# switch_eval_box_redo_v2.net
KiCad netlist of a schematic drawn in EAGLE
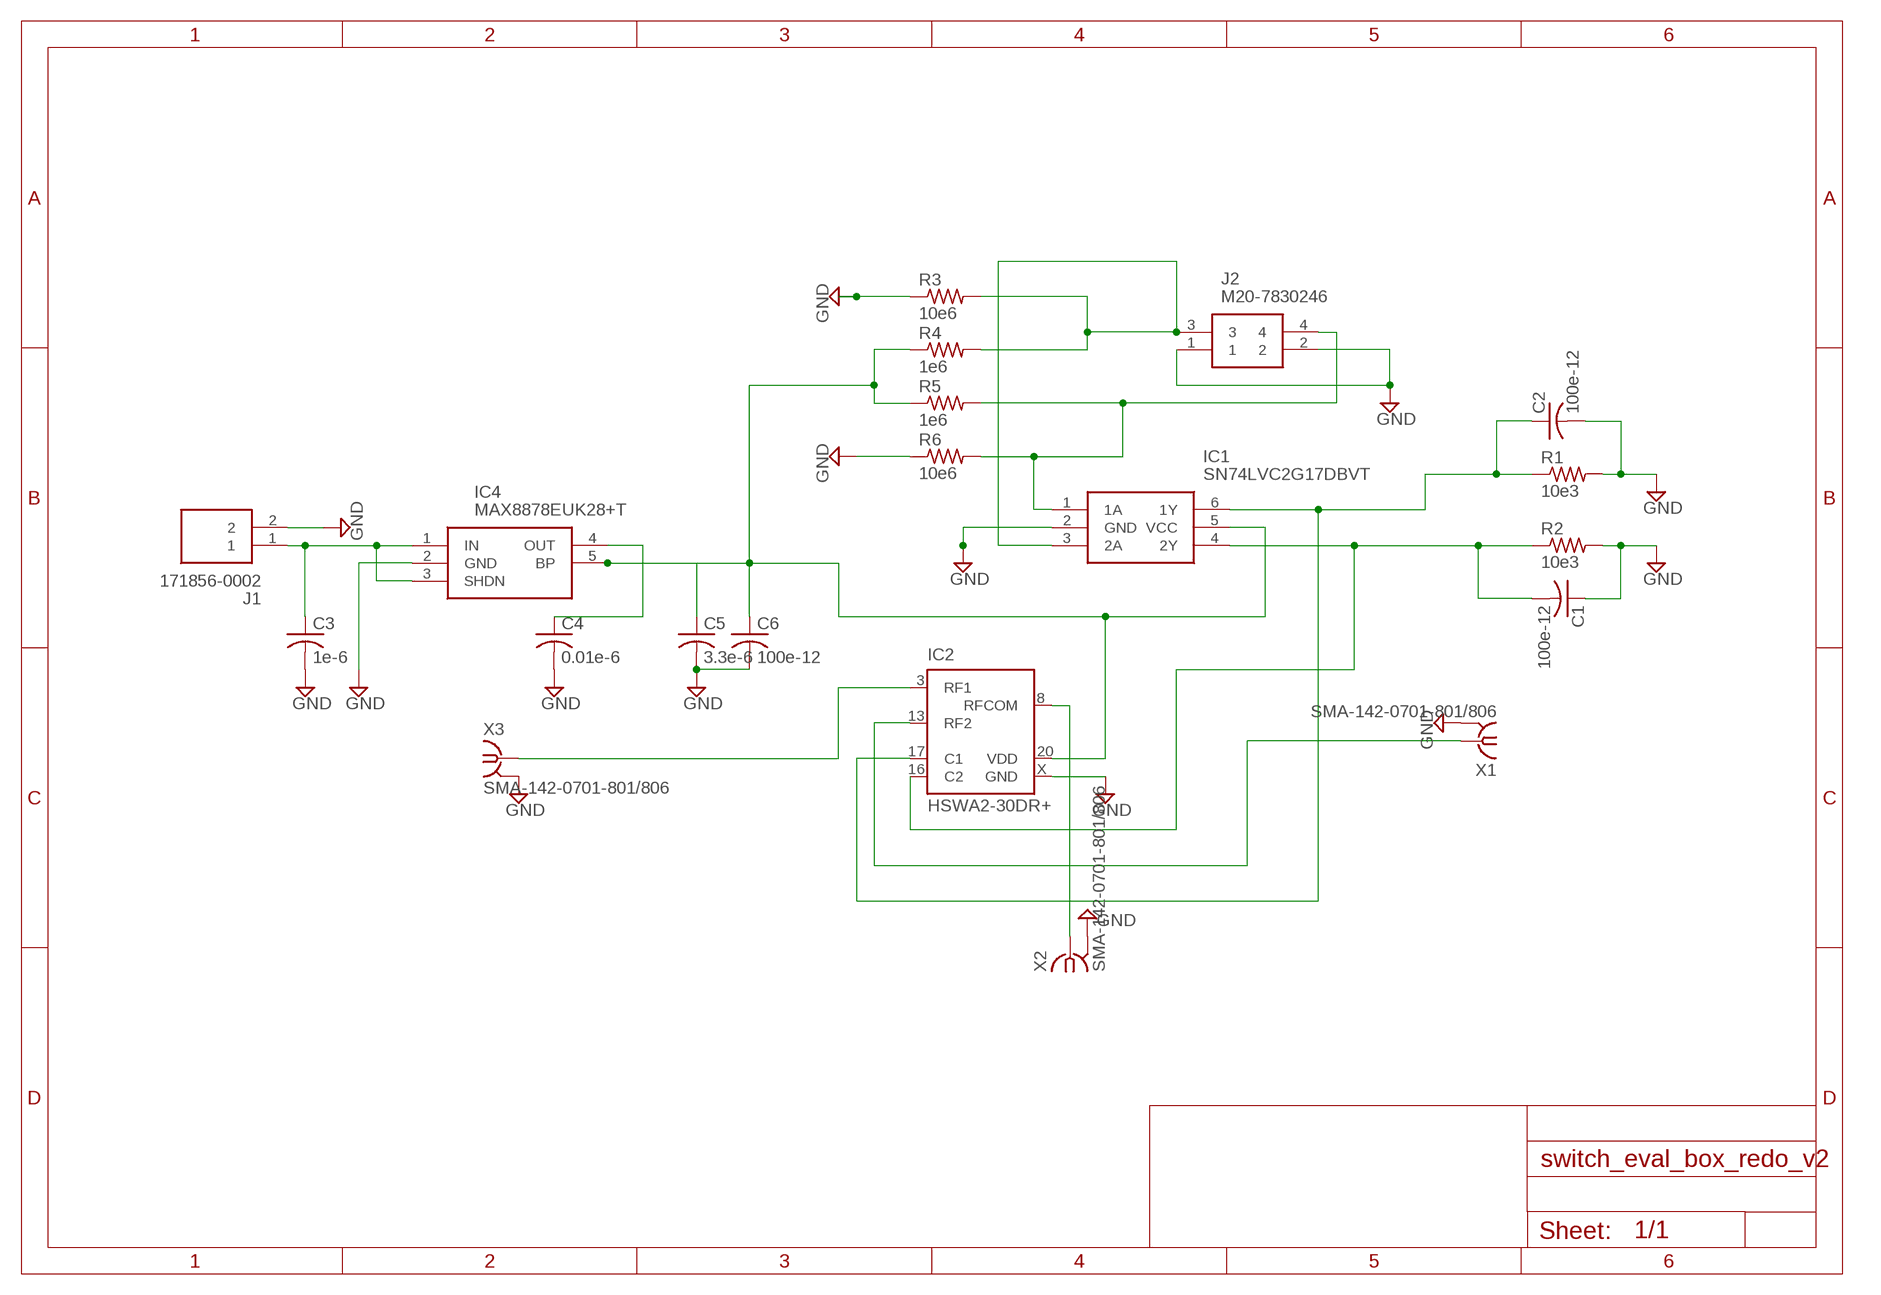
[diagram p0: schematic, sheet 1]

(export (version "E")
  (design (tool "Eeschema 10.0.6"))
  (components
    (comp (ref "C1")
      (value "100e-12")
      (footprint "eagle-import:C0603")
      (libsource (lib "eagle-import") (part "C-USC0603"))
    )
    (comp (ref "C2")
      (value "100e-12")
      (footprint "eagle-import:C0603")
      (libsource (lib "eagle-import") (part "C-USC0603"))
    )
    (comp (ref "C3")
      (value "1e-6")
      (footprint "eagle-import:C0603")
      (libsource (lib "eagle-import") (part "C-USC0603"))
    )
    (comp (ref "C4")
      (value "0.01e-6")
      (footprint "eagle-import:C0603")
      (libsource (lib "eagle-import") (part "C-USC0603"))
    )
    (comp (ref "C5")
      (value "3.3e-6")
      (footprint "eagle-import:C0603")
      (libsource (lib "eagle-import") (part "C-USC0603"))
    )
    (comp (ref "C6")
      (value "100e-12")
      (footprint "eagle-import:C0603")
      (libsource (lib "eagle-import") (part "C-USC0603"))
    )
    (comp (ref "IC1")
      (value "SN74LVC2G17DBVT")
      (footprint "eagle-import:SOT95P280X145-6N")
      (fields
        (field (name "MOUSER_PART_NUMBER") "595-SN74LVC2G17DBVT")
        (field (name "RS_PART_NUMBER") "6628944P")
      )
      (libsource (lib "eagle-import") (part "SN74LVC2G17DBVT"))
    )
    (comp (ref "IC2")
      (value "HSWA2-30DR+")
      (footprint "eagle-import:DG983-1")
      (libsource (lib "eagle-import") (part "HSWA2-30DR+"))
    )
    (comp (ref "IC4")
      (value "MAX8878EUK28+T")
      (footprint "eagle-import:SOT95P280X145-5N")
      (libsource (lib "eagle-import") (part "MAX8878EUK28+T"))
    )
    (comp (ref "J1")
      (value "171856-0002")
      (footprint "eagle-import:SHDR2W90P0X254_1X2_493X635X106")
      (fields
        (field (name "MOUSER_PART_NUMBER") "538-171856-0002")
        (field (name "RS_PART_NUMBER") "7922884P")
      )
      (libsource (lib "eagle-import") (part "171856-0002"))
    )
    (comp (ref "J2")
      (value "M20-7830246")
      (footprint "eagle-import:M207830246")
      (fields
        (field (name "MOUSER_PART_NUMBER") "855-M20-7830246")
        (field (name "RS_PART_NUMBER") "6816839P")
      )
      (libsource (lib "eagle-import") (part "M20-7830246"))
    )
    (comp (ref "R1")
      (value "10e3")
      (footprint "eagle-import:R0603")
      (libsource (lib "eagle-import") (part "R-US_R0603"))
    )
    (comp (ref "R2")
      (value "10e3")
      (footprint "eagle-import:R0603")
      (libsource (lib "eagle-import") (part "R-US_R0603"))
    )
    (comp (ref "R3")
      (value "10e6")
      (footprint "eagle-import:R0603")
      (libsource (lib "eagle-import") (part "R-US_R0603"))
    )
    (comp (ref "R4")
      (value "1e6")
      (footprint "eagle-import:R0603")
      (libsource (lib "eagle-import") (part "R-US_R0603"))
    )
    (comp (ref "R5")
      (value "1e6")
      (footprint "eagle-import:R0603")
      (libsource (lib "eagle-import") (part "R-US_R0603"))
    )
    (comp (ref "R6")
      (value "10e6")
      (footprint "eagle-import:R0603")
      (libsource (lib "eagle-import") (part "R-US_R0603"))
    )
    (comp (ref "X1")
      (value "SMA-142-0701-801/806")
      (footprint "eagle-import:J502-ND-142-0701-801_806")
      (fields (field (name "MF") "JOHNSON COMPONENTS") (field (name "MPN") "142-0701-801"))
      (libsource (lib "eagle-import") (part "SMA-142-0701-801/806"))
    )
    (comp (ref "X2")
      (value "SMA-142-0701-801/806")
      (footprint "eagle-import:J502-ND-142-0701-801_806")
      (fields (field (name "MF") "JOHNSON COMPONENTS") (field (name "MPN") "142-0701-801"))
      (libsource (lib "eagle-import") (part "SMA-142-0701-801/806"))
    )
    (comp (ref "X3")
      (value "SMA-142-0701-801/806")
      (footprint "eagle-import:J502-ND-142-0701-801_806")
      (fields (field (name "MF") "JOHNSON COMPONENTS") (field (name "MPN") "142-0701-801"))
      (libsource (lib "eagle-import") (part "SMA-142-0701-801/806"))
    )
  )
  (nets
    (net (code "1") (name "GND") (class "Default")
      (node (ref "C1") (pin "1") (pinfunction "1_1") (pintype "passive"))
      (node (ref "C2") (pin "2") (pinfunction "2_2") (pintype "passive"))
      (node (ref "C3") (pin "2") (pinfunction "2_2") (pintype "passive"))
      (node (ref "C4") (pin "2") (pinfunction "2_2") (pintype "passive"))
      (node (ref "C5") (pin "2") (pinfunction "2_2") (pintype "passive"))
      (node (ref "C6") (pin "2") (pinfunction "2_2") (pintype "passive"))
      (node (ref "IC1") (pin "2") (pinfunction "GND_2") (pintype "bidirectional"))
      (node (ref "IC2") (pin "X") (pinfunction "GND_X") (pintype "power_in"))
      (node (ref "IC4") (pin "2") (pinfunction "GND_2") (pintype "power_in"))
      (node (ref "J1") (pin "2") (pinfunction "2_2") (pintype "bidirectional"))
      (node (ref "J2") (pin "1") (pinfunction "1_1") (pintype "bidirectional"))
      (node (ref "J2") (pin "2") (pinfunction "2_2") (pintype "bidirectional"))
      (node (ref "R1") (pin "2") (pinfunction "2_2") (pintype "passive"))
      (node (ref "R2") (pin "2") (pinfunction "2_2") (pintype "passive"))
      (node (ref "R3") (pin "1") (pinfunction "1_1") (pintype "passive"))
      (node (ref "R6") (pin "1") (pinfunction "1_1") (pintype "passive"))
      (node (ref "X1") (pin "G@1") (pinfunction "2_G@1") (pintype "passive"))
      (node (ref "X1") (pin "G@2") (pinfunction "2_G@2") (pintype "passive"))
      (node (ref "X1") (pin "G@3") (pinfunction "2_G@3") (pintype "passive"))
      (node (ref "X1") (pin "G@4") (pinfunction "2_G@4") (pintype "passive"))
      (node (ref "X2") (pin "G@1") (pinfunction "2_G@1") (pintype "passive"))
      (node (ref "X2") (pin "G@2") (pinfunction "2_G@2") (pintype "passive"))
      (node (ref "X2") (pin "G@3") (pinfunction "2_G@3") (pintype "passive"))
      (node (ref "X2") (pin "G@4") (pinfunction "2_G@4") (pintype "passive"))
      (node (ref "X3") (pin "G@1") (pinfunction "2_G@1") (pintype "passive"))
      (node (ref "X3") (pin "G@2") (pinfunction "2_G@2") (pintype "passive"))
      (node (ref "X3") (pin "G@3") (pinfunction "2_G@3") (pintype "passive"))
      (node (ref "X3") (pin "G@4") (pinfunction "2_G@4") (pintype "passive"))
    )
    (net (code "2") (name "Net-(IC1-1A)") (class "Default")
      (node (ref "IC1") (pin "1") (pinfunction "1A_1") (pintype "bidirectional"))
      (node (ref "J2") (pin "4") (pinfunction "4_4") (pintype "bidirectional"))
      (node (ref "R5") (pin "2") (pinfunction "2_2") (pintype "passive"))
      (node (ref "R6") (pin "2") (pinfunction "2_2") (pintype "passive"))
    )
    (net (code "3") (name "Net-(IC1-1Y)") (class "Default")
      (node (ref "C2") (pin "1") (pinfunction "1_1") (pintype "passive"))
      (node (ref "IC1") (pin "6") (pinfunction "1Y_6") (pintype "bidirectional"))
      (node (ref "IC2") (pin "17") (pinfunction "C1_17") (pintype "passive"))
      (node (ref "R1") (pin "1") (pinfunction "1_1") (pintype "passive"))
    )
    (net (code "4") (name "Net-(IC1-2A)") (class "Default")
      (node (ref "IC1") (pin "3") (pinfunction "2A_3") (pintype "bidirectional"))
      (node (ref "J2") (pin "3") (pinfunction "3_3") (pintype "bidirectional"))
      (node (ref "R3") (pin "2") (pinfunction "2_2") (pintype "passive"))
      (node (ref "R4") (pin "2") (pinfunction "2_2") (pintype "passive"))
    )
    (net (code "5") (name "Net-(IC1-2Y)") (class "Default")
      (node (ref "C1") (pin "2") (pinfunction "2_2") (pintype "passive"))
      (node (ref "IC1") (pin "4") (pinfunction "2Y_4") (pintype "bidirectional"))
      (node (ref "IC2") (pin "16") (pinfunction "C2_16") (pintype "passive"))
      (node (ref "R2") (pin "1") (pinfunction "1_1") (pintype "passive"))
    )
    (net (code "6") (name "Net-(IC1-VCC)") (class "Default")
      (node (ref "C5") (pin "1") (pinfunction "1_1") (pintype "passive"))
      (node (ref "C6") (pin "1") (pinfunction "1_1") (pintype "passive"))
      (node (ref "IC1") (pin "5") (pinfunction "VCC_5") (pintype "bidirectional"))
      (node (ref "IC2") (pin "20") (pinfunction "VDD_20") (pintype "input"))
      (node (ref "IC4") (pin "5") (pinfunction "BP_5") (pintype "bidirectional"))
      (node (ref "R4") (pin "1") (pinfunction "1_1") (pintype "passive"))
      (node (ref "R5") (pin "1") (pinfunction "1_1") (pintype "passive"))
    )
    (net (code "7") (name "Net-(IC2A-RF1)") (class "Default")
      (node (ref "IC2") (pin "3") (pinfunction "RF1_3") (pintype "passive"))
      (node (ref "X3") (pin "1") (pinfunction "1_1") (pintype "passive"))
    )
    (net (code "8") (name "Net-(IC2A-RF2)") (class "Default")
      (node (ref "IC2") (pin "13") (pinfunction "RF2_13") (pintype "passive"))
      (node (ref "X1") (pin "1") (pinfunction "1_1") (pintype "passive"))
    )
    (net (code "9") (name "Net-(IC2A-RFCOM)") (class "Default")
      (node (ref "IC2") (pin "8") (pinfunction "RFCOM_8") (pintype "passive"))
      (node (ref "X2") (pin "1") (pinfunction "1_1") (pintype "passive"))
    )
    (net (code "10") (name "Net-(IC4-IN)") (class "Default")
      (node (ref "C3") (pin "1") (pinfunction "1_1") (pintype "passive"))
      (node (ref "IC4") (pin "1") (pinfunction "IN_1") (pintype "input"))
      (node (ref "IC4") (pin "3") (pinfunction "SHDN_3") (pintype "bidirectional"))
      (node (ref "J1") (pin "1") (pinfunction "1_1") (pintype "bidirectional"))
    )
    (net (code "11") (name "Net-(IC4-OUT)") (class "Default")
      (node (ref "C4") (pin "1") (pinfunction "1_1") (pintype "passive"))
      (node (ref "IC4") (pin "4") (pinfunction "OUT_4") (pintype "output"))
    )
  )
)
